# sparkfun-photon_p1.net
KiCad netlist of a schematic drawn in EAGLE
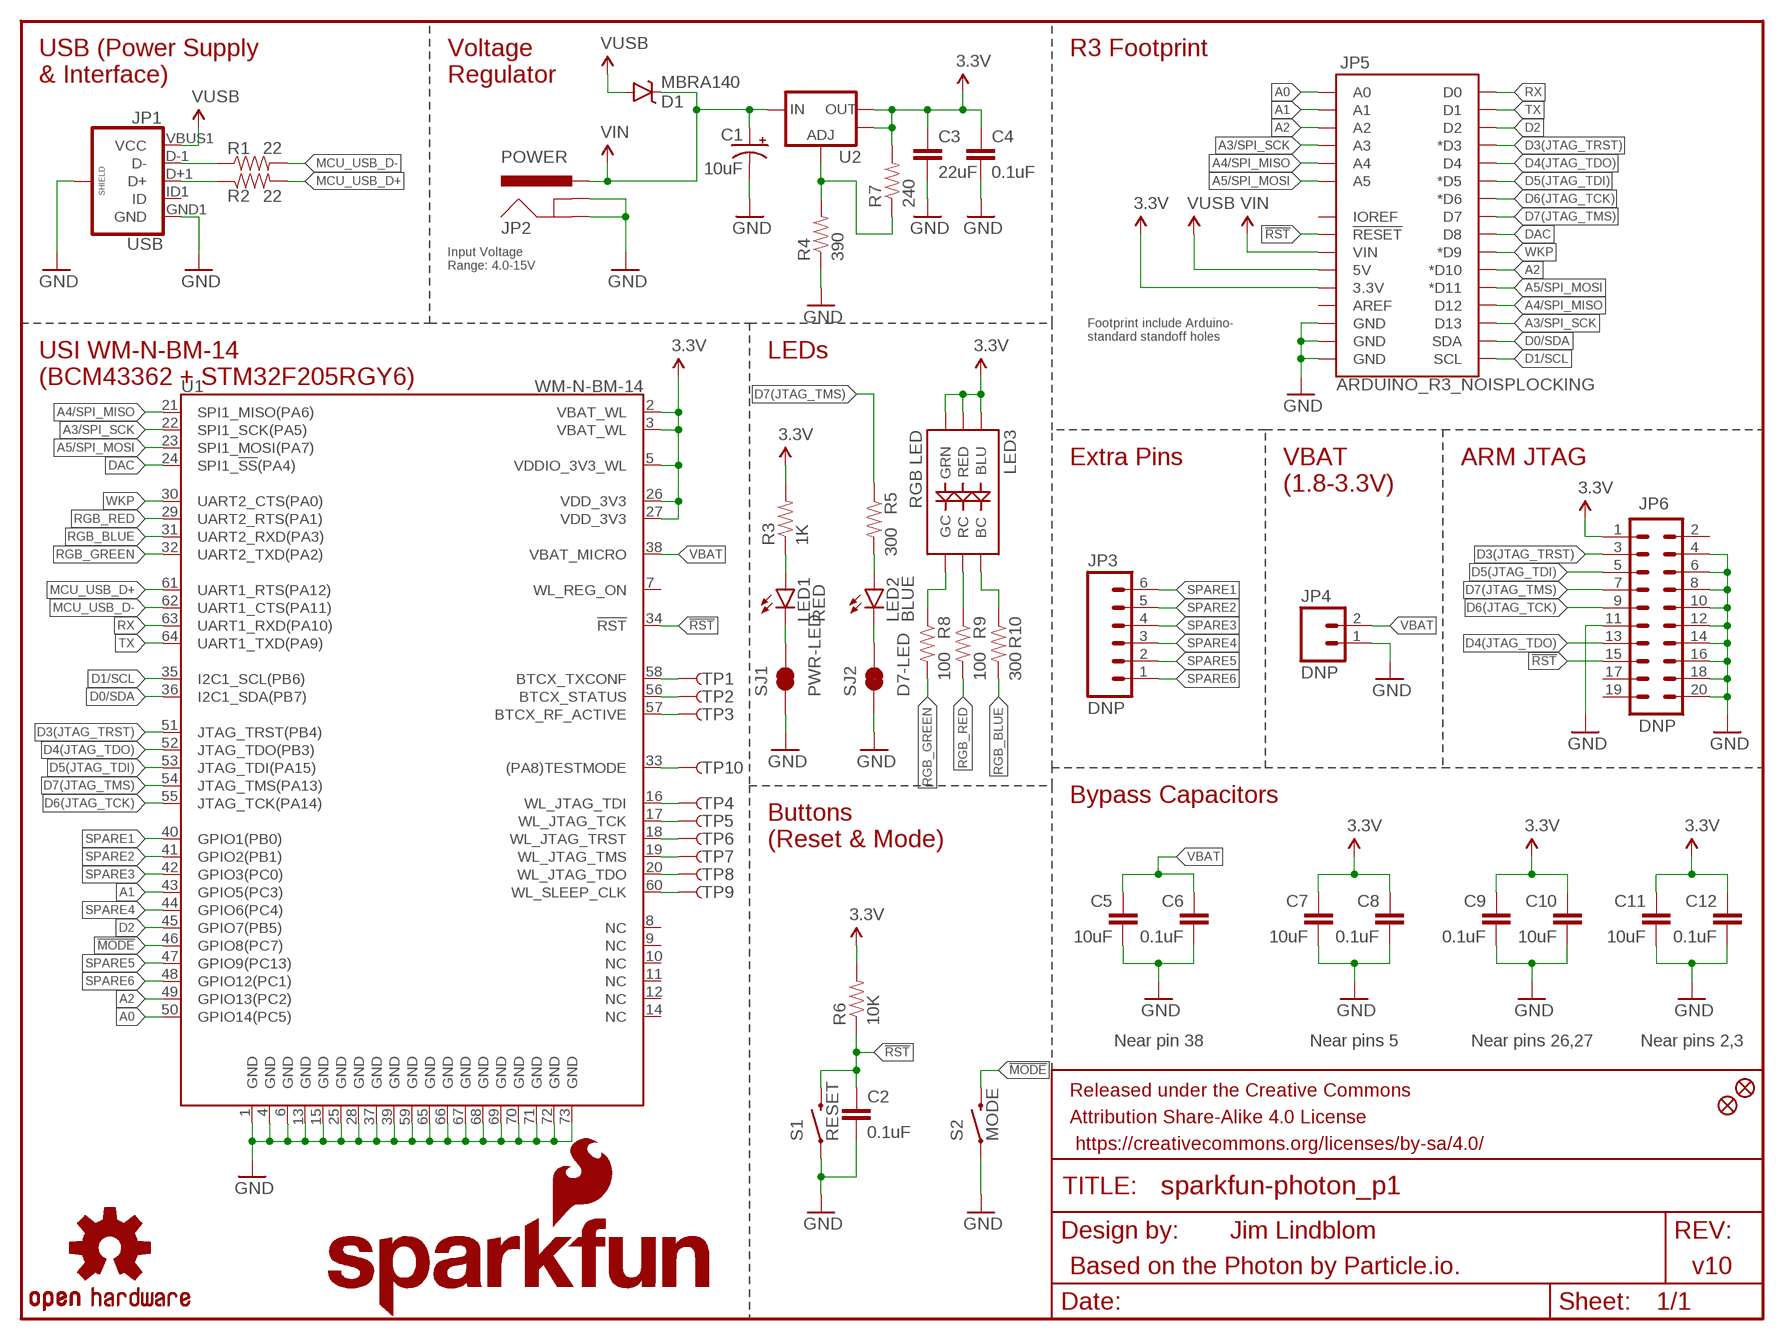
[diagram p0: schematic, sheet 1]

(export (version "E")
  (design (tool "Eeschema 10.0.6"))
  (components
    (comp (ref "C1")
      (value "10uF")
      (footprint "eagle-import:EIA3216")
      (libsource (lib "eagle-import") (part "10UF-16V-10%(TANT)"))
    )
    (comp (ref "C2")
      (value "0.1uF")
      (footprint "eagle-import:0603-CAP")
      (libsource (lib "eagle-import") (part "0.1UF-25V(+80/-20%)(0603)"))
    )
    (comp (ref "C3")
      (value "22uF")
      (footprint "eagle-import:0805")
      (libsource (lib "eagle-import") (part "22UF-6.3V-20%(0805)"))
    )
    (comp (ref "C4")
      (value "0.1uF")
      (footprint "eagle-import:0603-CAP")
      (libsource (lib "eagle-import") (part "0.1UF-25V(+80/-20%)(0603)"))
    )
    (comp (ref "C5")
      (value "10uF")
      (footprint "eagle-import:0603-CAP")
      (libsource (lib "eagle-import") (part "10UF-6.3V-20%(0603)"))
    )
    (comp (ref "C6")
      (value "0.1uF")
      (footprint "eagle-import:0603-CAP")
      (libsource (lib "eagle-import") (part "0.1UF-25V(+80/-20%)(0603)"))
    )
    (comp (ref "C7")
      (value "10uF")
      (footprint "eagle-import:0603-CAP")
      (libsource (lib "eagle-import") (part "10UF-6.3V-20%(0603)"))
    )
    (comp (ref "C8")
      (value "0.1uF")
      (footprint "eagle-import:0603-CAP")
      (libsource (lib "eagle-import") (part "0.1UF-25V(+80/-20%)(0603)"))
    )
    (comp (ref "C9")
      (value "0.1uF")
      (footprint "eagle-import:0603-CAP")
      (libsource (lib "eagle-import") (part "0.1UF-25V(+80/-20%)(0603)"))
    )
    (comp (ref "C10")
      (value "10uF")
      (footprint "eagle-import:0603-CAP")
      (libsource (lib "eagle-import") (part "10UF-6.3V-20%(0603)"))
    )
    (comp (ref "C11")
      (value "10uF")
      (footprint "eagle-import:0603-CAP")
      (libsource (lib "eagle-import") (part "10UF-6.3V-20%(0603)"))
    )
    (comp (ref "C12")
      (value "0.1uF")
      (footprint "eagle-import:0603-CAP")
      (libsource (lib "eagle-import") (part "0.1UF-25V(+80/-20%)(0603)"))
    )
    (comp (ref "D1")
      (value "MBRA140")
      (footprint "eagle-import:SMA-DIODE")
      (libsource (lib "eagle-import") (part "DIODE-SCHOTTKY-MBRA140"))
    )
    (comp (ref "FID1")
      (value "FIDUCIAL1X2")
      (footprint "eagle-import:FIDUCIAL-1X2")
      (libsource (lib "eagle-import") (part "FIDUCIAL1X2"))
    )
    (comp (ref "FID2")
      (value "FIDUCIAL1X2")
      (footprint "eagle-import:FIDUCIAL-1X2")
      (libsource (lib "eagle-import") (part "FIDUCIAL1X2"))
    )
    (comp (ref "FRAME1")
      (value "FRAME-LETTER")
      (footprint "eagle-import:CREATIVE_COMMONS")
      (fields (field (name "DESIGNER") "Jim Lindblom"))
      (libsource (lib "eagle-import") (part "FRAME-LETTER"))
    )
    (comp (ref "JP1")
      (value "USB")
      (footprint "eagle-import:USB-B-MICRO-SMD_V03")
      (libsource (lib "eagle-import") (part "USB_MICROB_PLUGCONN-11752"))
    )
    (comp (ref "JP2")
      (value "POWER")
      (footprint "eagle-import:POWER_JACK_PTH_LOCK")
      (libsource (lib "eagle-import") (part "POWER_JACKPTH_LOCK"))
    )
    (comp (ref "JP3")
      (value "DNP")
      (footprint "eagle-import:1X06")
      (libsource (lib "eagle-import") (part "M06SILK_FEMALE_PTH"))
    )
    (comp (ref "JP4")
      (value "DNP")
      (footprint "eagle-import:1X02")
      (libsource (lib "eagle-import") (part "M02PTH"))
    )
    (comp (ref "JP5")
      (value "ARDUINO_R3_NOISPLOCKING")
      (footprint "eagle-import:ARDUINO_R3_NOISP_LOCKING")
      (libsource (lib "eagle-import") (part "ARDUINO_R3_NOISPLOCKING"))
    )
    (comp (ref "JP6")
      (value "DNP")
      (footprint "eagle-import:2X10")
      (libsource (lib "eagle-import") (part "M10X2"))
    )
    (comp (ref "LED1")
      (value "RED")
      (footprint "eagle-import:LED-1206")
      (libsource (lib "eagle-import") (part "LED-RED1206"))
    )
    (comp (ref "LED2")
      (value "BLUE")
      (footprint "eagle-import:LED-1206")
      (libsource (lib "eagle-import") (part "LED-BLUE1206"))
    )
    (comp (ref "LED3")
      (value "RGB LED")
      (footprint "eagle-import:PLCC-6-LED")
      (libsource (lib "eagle-import") (part "LED-TRICOLOR-NO-COMPLCC-6-SMD"))
    )
    (comp (ref "LOGO1")
      (value "OSHW-LOGOM")
      (footprint "eagle-import:OSHW-LOGO-M")
      (libsource (lib "eagle-import") (part "OSHW-LOGOM"))
    )
    (comp (ref "LOGO2")
      (value "SFE_LOGO_NAME_FLAME.2_INCH")
      (footprint "eagle-import:SFE_LOGO_NAME_FLAME_.2")
      (libsource (lib "eagle-import") (part "SFE_LOGO_NAME_FLAME.2_INCH"))
    )
    (comp (ref "LOGO3")
      (value "SFE_LOGO_NAME_FLAME.4_INCH")
      (footprint "eagle-import:SFE_LOGO_NAME_FLAME_.4")
      (libsource (lib "eagle-import") (part "SFE_LOGO_NAME_FLAME.4_INCH"))
    )
    (comp (ref "R1")
      (value "22")
      (footprint "eagle-import:0603-RES")
      (libsource (lib "eagle-import") (part "22OHM1/10W1%(0603)"))
    )
    (comp (ref "R2")
      (value "22")
      (footprint "eagle-import:0603-RES")
      (libsource (lib "eagle-import") (part "22OHM1/10W1%(0603)"))
    )
    (comp (ref "R3")
      (value "1K")
      (footprint "eagle-import:0603-RES")
      (libsource (lib "eagle-import") (part "1KOHM-1/10W-1%(0603)"))
    )
    (comp (ref "R4")
      (value "390")
      (footprint "eagle-import:0603-RES")
      (libsource (lib "eagle-import") (part "390OHM1/10W1%(0603)"))
    )
    (comp (ref "R5")
      (value "300")
      (footprint "eagle-import:0603-RES")
      (libsource (lib "eagle-import") (part "300OHM-1/10W-1%(0603)"))
    )
    (comp (ref "R6")
      (value "10K")
      (footprint "eagle-import:0603-RES")
      (libsource (lib "eagle-import") (part "10KOHM-1/10W-1%(0603)0603"))
    )
    (comp (ref "R7")
      (value "240")
      (footprint "eagle-import:0603-RES")
      (libsource (lib "eagle-import") (part "240OHM1/10W1%(0603)"))
    )
    (comp (ref "R8")
      (value "100")
      (footprint "eagle-import:0603-RES")
      (libsource (lib "eagle-import") (part "100OHM-1/10W-1%(0603)"))
    )
    (comp (ref "R9")
      (value "100")
      (footprint "eagle-import:0603-RES")
      (libsource (lib "eagle-import") (part "100OHM-1/10W-1%(0603)"))
    )
    (comp (ref "R10")
      (value "300")
      (footprint "eagle-import:0603-RES")
      (libsource (lib "eagle-import") (part "300OHM-1/10W-1%(0603)"))
    )
    (comp (ref "S1")
      (value "RESET")
      (footprint "eagle-import:TACTILE-PTH")
      (libsource (lib "eagle-import") (part "SWITCH-MOMENTARY-2PTH"))
    )
    (comp (ref "S2")
      (value "MODE")
      (footprint "eagle-import:TACTILE-PTH")
      (libsource (lib "eagle-import") (part "SWITCH-MOMENTARY-2PTH"))
    )
    (comp (ref "SJ1")
      (value "PWR-LED")
      (footprint "eagle-import:PAD-JUMPER-2-NC_BY_TRACE_YES_SILK")
      (libsource (lib "eagle-import") (part "JUMPER-PAD-2-NC_BY_TRACE"))
    )
    (comp (ref "SJ2")
      (value "D7-LED")
      (footprint "eagle-import:PAD-JUMPER-2-NC_BY_TRACE_YES_SILK")
      (libsource (lib "eagle-import") (part "JUMPER-PAD-2-NC_BY_TRACE"))
    )
    (comp (ref "TP1")
      (value "TEST-POINTTP_15TH_THRU")
      (footprint "eagle-import:TP_15TH")
      (libsource (lib "eagle-import") (part "TEST-POINTTP_15TH_THRU"))
    )
    (comp (ref "TP2")
      (value "TEST-POINTTP_15TH_THRU")
      (footprint "eagle-import:TP_15TH")
      (libsource (lib "eagle-import") (part "TEST-POINTTP_15TH_THRU"))
    )
    (comp (ref "TP3")
      (value "TEST-POINTTP_15TH_THRU")
      (footprint "eagle-import:TP_15TH")
      (libsource (lib "eagle-import") (part "TEST-POINTTP_15TH_THRU"))
    )
    (comp (ref "TP4")
      (value "TEST-POINTTP_15TH_THRU")
      (footprint "eagle-import:TP_15TH")
      (libsource (lib "eagle-import") (part "TEST-POINTTP_15TH_THRU"))
    )
    (comp (ref "TP5")
      (value "TEST-POINTTP_15TH_THRU")
      (footprint "eagle-import:TP_15TH")
      (libsource (lib "eagle-import") (part "TEST-POINTTP_15TH_THRU"))
    )
    (comp (ref "TP6")
      (value "TEST-POINTTP_15TH_THRU")
      (footprint "eagle-import:TP_15TH")
      (libsource (lib "eagle-import") (part "TEST-POINTTP_15TH_THRU"))
    )
    (comp (ref "TP7")
      (value "TEST-POINTTP_15TH_THRU")
      (footprint "eagle-import:TP_15TH")
      (libsource (lib "eagle-import") (part "TEST-POINTTP_15TH_THRU"))
    )
    (comp (ref "TP8")
      (value "TEST-POINTTP_15TH_THRU")
      (footprint "eagle-import:TP_15TH")
      (libsource (lib "eagle-import") (part "TEST-POINTTP_15TH_THRU"))
    )
    (comp (ref "TP9")
      (value "TEST-POINTTP_15TH_THRU")
      (footprint "eagle-import:TP_15TH")
      (libsource (lib "eagle-import") (part "TEST-POINTTP_15TH_THRU"))
    )
    (comp (ref "TP10")
      (value "TEST-POINTTP_15TH_THRU")
      (footprint "eagle-import:TP_15TH")
      (libsource (lib "eagle-import") (part "TEST-POINTTP_15TH_THRU"))
    )
    (comp (ref "U1")
      (value "WM-N-BM-14")
      (footprint "eagle-import:WM-N-BM-14")
      (libsource (lib "eagle-import") (part "WM-N-BM-14"))
    )
    (comp (ref "U2")
      (value "V_REG_LM1117SOT223")
      (footprint "eagle-import:SOT223")
      (libsource (lib "eagle-import") (part "V_REG_LM1117SOT223"))
    )
  )
  (nets
    (net (code "1") (name "/~{MODE}") (class "Default")
      (node (ref "S2") (pin "3") (pinfunction "2_3") (pintype "passive"))
      (node (ref "U1") (pin "46") (pinfunction "GPIO8(PC7)_46") (pintype "bidirectional"))
    )
    (net (code "2") (name "/~{RST}") (class "Default")
      (node (ref "C2") (pin "1") (pinfunction "1_1") (pintype "passive"))
      (node (ref "JP5") (pin "RESET@1") (pinfunction "~{RESET}_RESET@1") (pintype "bidirectional"))
      (node (ref "JP6") (pin "15") (pinfunction "15_15") (pintype "passive"))
      (node (ref "R6") (pin "1") (pinfunction "1_1") (pintype "passive"))
      (node (ref "S1") (pin "3") (pinfunction "2_3") (pintype "passive"))
      (node (ref "U1") (pin "34") (pinfunction "~{RST}_34") (pintype "bidirectional"))
    )
    (net (code "3") (name "3.3V") (class "Default")
      (node (ref "C10") (pin "1") (pinfunction "1_1") (pintype "passive"))
      (node (ref "C11") (pin "1") (pinfunction "1_1") (pintype "passive"))
      (node (ref "C12") (pin "1") (pinfunction "1_1") (pintype "passive"))
      (node (ref "C3") (pin "1") (pinfunction "1_1") (pintype "passive"))
      (node (ref "C4") (pin "1") (pinfunction "1_1") (pintype "passive"))
      (node (ref "C7") (pin "1") (pinfunction "1_1") (pintype "passive"))
      (node (ref "C8") (pin "1") (pinfunction "1_1") (pintype "passive"))
      (node (ref "C9") (pin "1") (pinfunction "1_1") (pintype "passive"))
      (node (ref "JP5") (pin "3.3V") (pinfunction "3.3V_3.3V") (pintype "bidirectional"))
      (node (ref "JP6") (pin "1") (pinfunction "1_1") (pintype "passive"))
      (node (ref "LED3") (pin "AB") (pinfunction "BLU_AB") (pintype "bidirectional"))
      (node (ref "LED3") (pin "AG") (pinfunction "GRN_AG") (pintype "bidirectional"))
      (node (ref "LED3") (pin "AR") (pinfunction "RED_AR") (pintype "bidirectional"))
      (node (ref "R3") (pin "2") (pinfunction "2_2") (pintype "passive"))
      (node (ref "R6") (pin "2") (pinfunction "2_2") (pintype "passive"))
      (node (ref "R7") (pin "2") (pinfunction "2_2") (pintype "passive"))
      (node (ref "U1") (pin "2") (pinfunction "VBAT_WL_2") (pintype "bidirectional"))
      (node (ref "U1") (pin "26") (pinfunction "VDD_3V3_26") (pintype "bidirectional"))
      (node (ref "U1") (pin "27") (pinfunction "VDD_3V3_27") (pintype "bidirectional"))
      (node (ref "U1") (pin "3") (pinfunction "VBAT_WL_3") (pintype "bidirectional"))
      (node (ref "U1") (pin "5") (pinfunction "VDDIO_3V3_WL_5") (pintype "bidirectional"))
      (node (ref "U2") (pin "2") (pinfunction "OUT_2") (pintype "output"))
      (node (ref "U2") (pin "4") (pinfunction "OUT_4") (pintype "output"))
    )
    (net (code "4") (name "A0") (class "Default")
      (node (ref "JP5") (pin "A0") (pinfunction "A0_A0") (pintype "bidirectional"))
      (node (ref "U1") (pin "50") (pinfunction "GPIO14(PC5)_50") (pintype "bidirectional"))
    )
    (net (code "5") (name "A1") (class "Default")
      (node (ref "JP5") (pin "A1") (pinfunction "A1_A1") (pintype "bidirectional"))
      (node (ref "U1") (pin "43") (pinfunction "GPIO5(PC3)_43") (pintype "bidirectional"))
    )
    (net (code "6") (name "A2") (class "Default")
      (node (ref "JP5") (pin "A2") (pinfunction "A2_A2") (pintype "bidirectional"))
      (node (ref "JP5") (pin "D10") (pinfunction "*D10_D10") (pintype "bidirectional"))
      (node (ref "U1") (pin "49") (pinfunction "GPIO13(PC2)_49") (pintype "bidirectional"))
    )
    (net (code "7") (name "A3{slash}SPI_SCK") (class "Default")
      (node (ref "JP5") (pin "A3") (pinfunction "A3_A3") (pintype "bidirectional"))
      (node (ref "JP5") (pin "D13") (pinfunction "D13_D13") (pintype "bidirectional"))
      (node (ref "U1") (pin "22") (pinfunction "SPI1_SCK(PA5)_22") (pintype "bidirectional"))
    )
    (net (code "8") (name "A4{slash}SPI_MISO") (class "Default")
      (node (ref "JP5") (pin "A4") (pinfunction "A4_A4") (pintype "bidirectional"))
      (node (ref "JP5") (pin "D12") (pinfunction "D12_D12") (pintype "bidirectional"))
      (node (ref "U1") (pin "21") (pinfunction "SPI1_MISO(PA6)_21") (pintype "bidirectional"))
    )
    (net (code "9") (name "A5{slash}SPI_MOSI") (class "Default")
      (node (ref "JP5") (pin "A5") (pinfunction "A5_A5") (pintype "bidirectional"))
      (node (ref "JP5") (pin "D11") (pinfunction "*D11_D11") (pintype "bidirectional"))
      (node (ref "U1") (pin "23") (pinfunction "SPI1_MOSI(PA7)_23") (pintype "bidirectional"))
    )
    (net (code "10") (name "D0{slash}SDA") (class "Default")
      (node (ref "JP5") (pin "SDA") (pinfunction "SDA_SDA") (pintype "bidirectional"))
      (node (ref "U1") (pin "36") (pinfunction "I2C1_SDA(PB7)_36") (pintype "bidirectional"))
    )
    (net (code "11") (name "D1{slash}SCL") (class "Default")
      (node (ref "JP5") (pin "SCL") (pinfunction "SCL_SCL") (pintype "bidirectional"))
      (node (ref "U1") (pin "35") (pinfunction "I2C1_SCL(PB6)_35") (pintype "bidirectional"))
    )
    (net (code "12") (name "D2") (class "Default")
      (node (ref "JP5") (pin "D2") (pinfunction "D2_D2") (pintype "bidirectional"))
      (node (ref "U1") (pin "45") (pinfunction "GPIO7(PB5)_45") (pintype "bidirectional"))
    )
    (net (code "13") (name "D3(JTAG_TRST)") (class "Default")
      (node (ref "JP5") (pin "D3") (pinfunction "*D3_D3") (pintype "bidirectional"))
      (node (ref "JP6") (pin "3") (pinfunction "3_3") (pintype "passive"))
      (node (ref "U1") (pin "51") (pinfunction "JTAG_TRST(PB4)_51") (pintype "bidirectional"))
    )
    (net (code "14") (name "D4(JTAG_TDO)") (class "Default")
      (node (ref "JP5") (pin "D4") (pinfunction "D4_D4") (pintype "bidirectional"))
      (node (ref "JP6") (pin "13") (pinfunction "13_13") (pintype "passive"))
      (node (ref "U1") (pin "52") (pinfunction "JTAG_TDO(PB3)_52") (pintype "bidirectional"))
    )
    (net (code "15") (name "D5(JTAG_TDI)") (class "Default")
      (node (ref "JP5") (pin "D5") (pinfunction "*D5_D5") (pintype "bidirectional"))
      (node (ref "JP6") (pin "5") (pinfunction "5_5") (pintype "passive"))
      (node (ref "U1") (pin "53") (pinfunction "JTAG_TDI(PA15)_53") (pintype "bidirectional"))
    )
    (net (code "16") (name "D6(JTAG_TCK)") (class "Default")
      (node (ref "JP5") (pin "D6") (pinfunction "*D6_D6") (pintype "bidirectional"))
      (node (ref "JP6") (pin "9") (pinfunction "9_9") (pintype "passive"))
      (node (ref "U1") (pin "55") (pinfunction "JTAG_TCK(PA14)_55") (pintype "bidirectional"))
    )
    (net (code "17") (name "D7(JTAG_TMS)") (class "Default")
      (node (ref "JP5") (pin "D7") (pinfunction "D7_D7") (pintype "bidirectional"))
      (node (ref "JP6") (pin "7") (pinfunction "7_7") (pintype "passive"))
      (node (ref "R5") (pin "1") (pinfunction "1_1") (pintype "passive"))
      (node (ref "U1") (pin "54") (pinfunction "JTAG_TMS(PA13)_54") (pintype "bidirectional"))
    )
    (net (code "18") (name "DAC") (class "Default")
      (node (ref "JP5") (pin "D8") (pinfunction "D8_D8") (pintype "bidirectional"))
      (node (ref "U1") (pin "24") (pinfunction "SPI1_~{SS}(PA4)_24") (pintype "bidirectional"))
    )
    (net (code "19") (name "GND") (class "Default")
      (node (ref "C1") (pin "C") (pinfunction "-_C") (pintype "passive"))
      (node (ref "C10") (pin "2") (pinfunction "2_2") (pintype "passive"))
      (node (ref "C11") (pin "2") (pinfunction "2_2") (pintype "passive"))
      (node (ref "C12") (pin "2") (pinfunction "2_2") (pintype "passive"))
      (node (ref "C2") (pin "2") (pinfunction "2_2") (pintype "passive"))
      (node (ref "C3") (pin "2") (pinfunction "2_2") (pintype "passive"))
      (node (ref "C4") (pin "2") (pinfunction "2_2") (pintype "passive"))
      (node (ref "C5") (pin "2") (pinfunction "2_2") (pintype "passive"))
      (node (ref "C6") (pin "2") (pinfunction "2_2") (pintype "passive"))
      (node (ref "C7") (pin "2") (pinfunction "2_2") (pintype "passive"))
      (node (ref "C8") (pin "2") (pinfunction "2_2") (pintype "passive"))
      (node (ref "C9") (pin "2") (pinfunction "2_2") (pintype "passive"))
      (node (ref "JP1") (pin "GND1") (pinfunction "GND_GND1") (pintype "bidirectional"))
      (node (ref "JP1") (pin "SHIELD1") (pinfunction "SHIELD_SHIELD1") (pintype "bidirectional"))
      (node (ref "JP1") (pin "SHIELD2") (pinfunction "SHIELD_SHIELD2") (pintype "bidirectional"))
      (node (ref "JP1") (pin "SHIELD3") (pinfunction "SHIELD_SHIELD3") (pintype "bidirectional"))
      (node (ref "JP2") (pin "GND") (pinfunction "GND_GND") (pintype "bidirectional"))
      (node (ref "JP2") (pin "GNDBREAK") (pinfunction "GNDBREAK_GNDBREAK") (pintype "bidirectional"))
      (node (ref "JP4") (pin "1") (pinfunction "1_1") (pintype "passive"))
      (node (ref "JP5") (pin "GND@1") (pinfunction "GND_GND@1") (pintype "bidirectional"))
      (node (ref "JP5") (pin "GND@2") (pinfunction "GND_GND@2") (pintype "bidirectional"))
      (node (ref "JP5") (pin "GND@3") (pinfunction "GND_GND@3") (pintype "bidirectional"))
      (node (ref "JP6") (pin "10") (pinfunction "10_10") (pintype "passive"))
      (node (ref "JP6") (pin "11") (pinfunction "11_11") (pintype "passive"))
      (node (ref "JP6") (pin "12") (pinfunction "12_12") (pintype "passive"))
      (node (ref "JP6") (pin "14") (pinfunction "14_14") (pintype "passive"))
      (node (ref "JP6") (pin "16") (pinfunction "16_16") (pintype "passive"))
      (node (ref "JP6") (pin "18") (pinfunction "18_18") (pintype "passive"))
      (node (ref "JP6") (pin "20") (pinfunction "20_20") (pintype "passive"))
      (node (ref "JP6") (pin "4") (pinfunction "4_4") (pintype "passive"))
      (node (ref "JP6") (pin "6") (pinfunction "6_6") (pintype "passive"))
      (node (ref "JP6") (pin "8") (pinfunction "8_8") (pintype "passive"))
      (node (ref "R4") (pin "1") (pinfunction "1_1") (pintype "passive"))
      (node (ref "S1") (pin "1") (pinfunction "1_1") (pintype "passive"))
      (node (ref "S2") (pin "1") (pinfunction "1_1") (pintype "passive"))
      (node (ref "SJ1") (pin "1") (pinfunction "1_1") (pintype "passive"))
      (node (ref "SJ2") (pin "1") (pinfunction "1_1") (pintype "passive"))
      (node (ref "U1") (pin "1") (pinfunction "GND_1") (pintype "bidirectional"))
      (node (ref "U1") (pin "13") (pinfunction "GND_13") (pintype "bidirectional"))
      (node (ref "U1") (pin "15") (pinfunction "GND_15") (pintype "bidirectional"))
      (node (ref "U1") (pin "25") (pinfunction "GND_25") (pintype "bidirectional"))
      (node (ref "U1") (pin "28") (pinfunction "GND_28") (pintype "bidirectional"))
      (node (ref "U1") (pin "37") (pinfunction "GND_37") (pintype "bidirectional"))
      (node (ref "U1") (pin "39") (pinfunction "GND_39") (pintype "bidirectional"))
      (node (ref "U1") (pin "4") (pinfunction "GND_4") (pintype "bidirectional"))
      (node (ref "U1") (pin "59") (pinfunction "GND_59") (pintype "bidirectional"))
      (node (ref "U1") (pin "6") (pinfunction "GND_6") (pintype "bidirectional"))
      (node (ref "U1") (pin "65") (pinfunction "GND_65") (pintype "bidirectional"))
      (node (ref "U1") (pin "66") (pinfunction "GND_66") (pintype "bidirectional"))
      (node (ref "U1") (pin "67") (pinfunction "GND_67") (pintype "bidirectional"))
      (node (ref "U1") (pin "68") (pinfunction "GND_68") (pintype "bidirectional"))
      (node (ref "U1") (pin "69") (pinfunction "GND_69") (pintype "bidirectional"))
      (node (ref "U1") (pin "70") (pinfunction "GND_70") (pintype "bidirectional"))
      (node (ref "U1") (pin "71") (pinfunction "GND_71") (pintype "bidirectional"))
      (node (ref "U1") (pin "72") (pinfunction "GND_72") (pintype "bidirectional"))
      (node (ref "U1") (pin "73") (pinfunction "GND_73") (pintype "bidirectional"))
    )
    (net (code "20") (name "MCU_USB_D+") (class "Default")
      (node (ref "R2") (pin "2") (pinfunction "2_2") (pintype "passive"))
      (node (ref "U1") (pin "61") (pinfunction "UART1_RTS(PA12)_61") (pintype "bidirectional"))
    )
    (net (code "21") (name "MCU_USB_D-") (class "Default")
      (node (ref "R1") (pin "2") (pinfunction "2_2") (pintype "passive"))
      (node (ref "U1") (pin "62") (pinfunction "UART1_CTS(PA11)_62") (pintype "bidirectional"))
    )
    (net (code "22") (name "Net-(JP1-D+)") (class "Default")
      (node (ref "JP1") (pin "D+1") (pinfunction "D+_D+1") (pintype "bidirectional"))
      (node (ref "R2") (pin "1") (pinfunction "1_1") (pintype "passive"))
    )
    (net (code "23") (name "Net-(JP1-D-)") (class "Default")
      (node (ref "JP1") (pin "D-1") (pinfunction "D-_D-1") (pintype "bidirectional"))
      (node (ref "R1") (pin "1") (pinfunction "1_1") (pintype "passive"))
    )
    (net (code "24") (name "Net-(LED1-PadA)") (class "Default")
      (node (ref "LED1") (pin "A") (pinfunction "A_A") (pintype "passive"))
      (node (ref "R3") (pin "1") (pinfunction "1_1") (pintype "passive"))
    )
    (net (code "25") (name "Net-(LED1-PadC)") (class "Default")
      (node (ref "LED1") (pin "C") (pinfunction "C_C") (pintype "passive"))
      (node (ref "SJ1") (pin "2") (pinfunction "2_2") (pintype "passive"))
    )
    (net (code "26") (name "Net-(LED2-PadA)") (class "Default")
      (node (ref "LED2") (pin "A") (pinfunction "A_A") (pintype "passive"))
      (node (ref "R5") (pin "2") (pinfunction "2_2") (pintype "passive"))
    )
    (net (code "27") (name "Net-(LED2-PadC)") (class "Default")
      (node (ref "LED2") (pin "C") (pinfunction "C_C") (pintype "passive"))
      (node (ref "SJ2") (pin "2") (pinfunction "2_2") (pintype "passive"))
    )
    (net (code "28") (name "Net-(LED3-BC)") (class "Default")
      (node (ref "LED3") (pin "CB") (pinfunction "BC_CB") (pintype "bidirectional"))
      (node (ref "R10") (pin "1") (pinfunction "1_1") (pintype "passive"))
    )
    (net (code "29") (name "Net-(LED3-GC)") (class "Default")
      (node (ref "LED3") (pin "CG") (pinfunction "GC_CG") (pintype "bidirectional"))
      (node (ref "R8") (pin "1") (pinfunction "1_1") (pintype "passive"))
    )
    (net (code "30") (name "Net-(LED3-RC)") (class "Default")
      (node (ref "LED3") (pin "CR") (pinfunction "RC_CR") (pintype "bidirectional"))
      (node (ref "R9") (pin "1") (pinfunction "1_1") (pintype "passive"))
    )
    (net (code "31") (name "Net-(TP1-1)") (class "Default")
      (node (ref "TP1") (pin "P$1") (pinfunction "1_P$1") (pintype "bidirectional"))
      (node (ref "U1") (pin "58") (pinfunction "BTCX_TXCONF_58") (pintype "bidirectional"))
    )
    (net (code "32") (name "Net-(TP2-1)") (class "Default")
      (node (ref "TP2") (pin "P$1") (pinfunction "1_P$1") (pintype "bidirectional"))
      (node (ref "U1") (pin "56") (pinfunction "BTCX_STATUS_56") (pintype "bidirectional"))
    )
    (net (code "33") (name "Net-(TP3-1)") (class "Default")
      (node (ref "TP3") (pin "P$1") (pinfunction "1_P$1") (pintype "bidirectional"))
      (node (ref "U1") (pin "57") (pinfunction "BTCX_RF_ACTIVE_57") (pintype "bidirectional"))
    )
    (net (code "34") (name "Net-(TP4-1)") (class "Default")
      (node (ref "TP4") (pin "P$1") (pinfunction "1_P$1") (pintype "bidirectional"))
      (node (ref "U1") (pin "16") (pinfunction "WL_JTAG_TDI_16") (pintype "bidirectional"))
    )
    (net (code "35") (name "Net-(TP5-1)") (class "Default")
      (node (ref "TP5") (pin "P$1") (pinfunction "1_P$1") (pintype "bidirectional"))
      (node (ref "U1") (pin "17") (pinfunction "WL_JTAG_TCK_17") (pintype "bidirectional"))
    )
    (net (code "36") (name "Net-(TP6-1)") (class "Default")
      (node (ref "TP6") (pin "P$1") (pinfunction "1_P$1") (pintype "bidirectional"))
      (node (ref "U1") (pin "18") (pinfunction "WL_JTAG_TRST_18") (pintype "bidirectional"))
    )
    (net (code "37") (name "Net-(TP7-1)") (class "Default")
      (node (ref "TP7") (pin "P$1") (pinfunction "1_P$1") (pintype "bidirectional"))
      (node (ref "U1") (pin "19") (pinfunction "WL_JTAG_TMS_19") (pintype "bidirectional"))
    )
    (net (code "38") (name "Net-(TP8-1)") (class "Default")
      (node (ref "TP8") (pin "P$1") (pinfunction "1_P$1") (pintype "bidirectional"))
      (node (ref "U1") (pin "20") (pinfunction "WL_JTAG_TDO_20") (pintype "bidirectional"))
    )
    (net (code "39") (name "Net-(TP9-1)") (class "Default")
      (node (ref "TP9") (pin "P$1") (pinfunction "1_P$1") (pintype "bidirectional"))
      (node (ref "U1") (pin "60") (pinfunction "WL_SLEEP_CLK_60") (pintype "bidirectional"))
    )
    (net (code "40") (name "Net-(TP10-1)") (class "Default")
      (node (ref "TP10") (pin "P$1") (pinfunction "1_P$1") (pintype "bidirectional"))
      (node (ref "U1") (pin "33") (pinfunction "(PA8)TESTMODE_33") (pintype "bidirectional"))
    )
    (net (code "41") (name "Net-(U2-ADJ)") (class "Default")
      (node (ref "R4") (pin "2") (pinfunction "2_2") (pintype "passive"))
      (node (ref "R7") (pin "1") (pinfunction "1_1") (pintype "passive"))
      (node (ref "U2") (pin "1") (pinfunction "ADJ_1") (pintype "input"))
    )
    (net (code "42") (name "RGB_BLUE") (class "Default")
      (node (ref "R10") (pin "2") (pinfunction "2_2") (pintype "passive"))
      (node (ref "U1") (pin "31") (pinfunction "UART2_RXD(PA3)_31") (pintype "bidirectional"))
    )
    (net (code "43") (name "RGB_GREEN") (class "Default")
      (node (ref "R8") (pin "2") (pinfunction "2_2") (pintype "passive"))
      (node (ref "U1") (pin "32") (pinfunction "UART2_TXD(PA2)_32") (pintype "bidirectional"))
    )
    (net (code "44") (name "RGB_RED") (class "Default")
      (node (ref "R9") (pin "2") (pinfunction "2_2") (pintype "passive"))
      (node (ref "U1") (pin "29") (pinfunction "UART2_RTS(PA1)_29") (pintype "bidirectional"))
    )
    (net (code "45") (name "RX") (class "Default")
      (node (ref "JP5") (pin "D0") (pinfunction "D0_D0") (pintype "bidirectional"))
      (node (ref "U1") (pin "63") (pinfunction "UART1_RXD(PA10)_63") (pintype "bidirectional"))
    )
    (net (code "46") (name "SPARE1") (class "Default")
      (node (ref "JP3") (pin "6") (pinfunction "6_6") (pintype "passive"))
      (node (ref "U1") (pin "40") (pinfunction "GPIO1(PB0)_40") (pintype "bidirectional"))
    )
    (net (code "47") (name "SPARE2") (class "Default")
      (node (ref "JP3") (pin "5") (pinfunction "5_5") (pintype "passive"))
      (node (ref "U1") (pin "41") (pinfunction "GPIO2(PB1)_41") (pintype "bidirectional"))
    )
    (net (code "48") (name "SPARE3") (class "Default")
      (node (ref "JP3") (pin "4") (pinfunction "4_4") (pintype "passive"))
      (node (ref "U1") (pin "42") (pinfunction "GPIO3(PC0)_42") (pintype "bidirectional"))
    )
    (net (code "49") (name "SPARE4") (class "Default")
      (node (ref "JP3") (pin "3") (pinfunction "3_3") (pintype "passive"))
      (node (ref "U1") (pin "44") (pinfunction "GPIO6(PC4)_44") (pintype "bidirectional"))
    )
    (net (code "50") (name "SPARE5") (class "Default")
      (node (ref "JP3") (pin "2") (pinfunction "2_2") (pintype "passive"))
      (node (ref "U1") (pin "47") (pinfunction "GPIO9(PC13)_47") (pintype "bidirectional"))
    )
    (net (code "51") (name "SPARE6") (class "Default")
      (node (ref "JP3") (pin "1") (pinfunction "1_1") (pintype "passive"))
      (node (ref "U1") (pin "48") (pinfunction "GPIO12(PC1)_48") (pintype "bidirectional"))
    )
    (net (code "52") (name "TX") (class "Default")
      (node (ref "JP5") (pin "D1") (pinfunction "D1_D1") (pintype "bidirectional"))
      (node (ref "U1") (pin "64") (pinfunction "UART1_TXD(PA9)_64") (pintype "bidirectional"))
    )
    (net (code "53") (name "VBAT") (class "Default")
      (node (ref "C5") (pin "1") (pinfunction "1_1") (pintype "passive"))
      (node (ref "C6") (pin "1") (pinfunction "1_1") (pintype "passive"))
      (node (ref "JP4") (pin "2") (pinfunction "2_2") (pintype "passive"))
      (node (ref "U1") (pin "38") (pinfunction "VBAT_MICRO_38") (pintype "bidirectional"))
    )
    (net (code "54") (name "VIN") (class "Default")
      (node (ref "C1") (pin "A") (pinfunction "+_A") (pintype "passive"))
      (node (ref "D1") (pin "C") (pinfunction "C_C") (pintype "passive"))
      (node (ref "JP2") (pin "PWR") (pinfunction "PWR_PWR") (pintype "bidirectional"))
      (node (ref "JP5") (pin "VIN") (pinfunction "VIN_VIN") (pintype "bidirectional"))
      (node (ref "U2") (pin "3") (pinfunction "IN_3") (pintype "input"))
    )
    (net (code "55") (name "VUSB") (class "Default")
      (node (ref "D1") (pin "A") (pinfunction "A_A") (pintype "passive"))
      (node (ref "JP1") (pin "VBUS1") (pinfunction "VCC_VBUS1") (pintype "bidirectional"))
      (node (ref "JP5") (pin "5V") (pinfunction "5V_5V") (pintype "bidirectional"))
    )
    (net (code "56") (name "WKP") (class "Default")
      (node (ref "JP5") (pin "D9") (pinfunction "*D9_D9") (pintype "bidirectional"))
      (node (ref "U1") (pin "30") (pinfunction "UART2_CTS(PA0)_30") (pintype "bidirectional"))
    )
    (net (code "57") (name "unconnected-(JP1-ID-PadID1)") (class "Default")
      (node (ref "JP1") (pin "ID1") (pinfunction "ID_ID1") (pintype "bidirectional"))
    )
    (net (code "58") (name "unconnected-(JP5-PadAREF)") (class "Default")
      (node (ref "JP5") (pin "AREF") (pinfunction "AREF_AREF") (pintype "bidirectional"))
    )
    (net (code "59") (name "unconnected-(JP5-PadIOREF)") (class "Default")
      (node (ref "JP5") (pin "IOREF") (pinfunction "IOREF_IOREF") (pintype "bidirectional"))
    )
    (net (code "60") (name "unconnected-(JP6-Pad2)") (class "Default")
      (node (ref "JP6") (pin "2") (pinfunction "2_2") (pintype "passive"))
    )
    (net (code "61") (name "unconnected-(JP6-Pad17)") (class "Default")
      (node (ref "JP6") (pin "17") (pinfunction "17_17") (pintype "passive"))
    )
    (net (code "62") (name "unconnected-(JP6-Pad19)") (class "Default")
      (node (ref "JP6") (pin "19") (pinfunction "19_19") (pintype "passive"))
    )
    (net (code "63") (name "unconnected-(U1-NC-Pad8)") (class "Default")
      (node (ref "U1") (pin "8") (pinfunction "NC_8") (pintype "bidirectional"))
    )
    (net (code "64") (name "unconnected-(U1-NC-Pad9)") (class "Default")
      (node (ref "U1") (pin "9") (pinfunction "NC_9") (pintype "bidirectional"))
    )
    (net (code "65") (name "unconnected-(U1-NC-Pad10)") (class "Default")
      (node (ref "U1") (pin "10") (pinfunction "NC_10") (pintype "bidirectional"))
    )
    (net (code "66") (name "unconnected-(U1-NC-Pad11)") (class "Default")
      (node (ref "U1") (pin "11") (pinfunction "NC_11") (pintype "bidirectional"))
    )
    (net (code "67") (name "unconnected-(U1-NC-Pad12)") (class "Default")
      (node (ref "U1") (pin "12") (pinfunction "NC_12") (pintype "bidirectional"))
    )
    (net (code "68") (name "unconnected-(U1-NC-Pad14)") (class "Default")
      (node (ref "U1") (pin "14") (pinfunction "NC_14") (pintype "bidirectional"))
    )
    (net (code "69") (name "unconnected-(U1-WL_REG_ON-Pad7)") (class "Default")
      (node (ref "U1") (pin "7") (pinfunction "WL_REG_ON_7") (pintype "bidirectional"))
    )
  )
)
